# UWB.net
KiCad netlist of a schematic drawn in Altium Designer
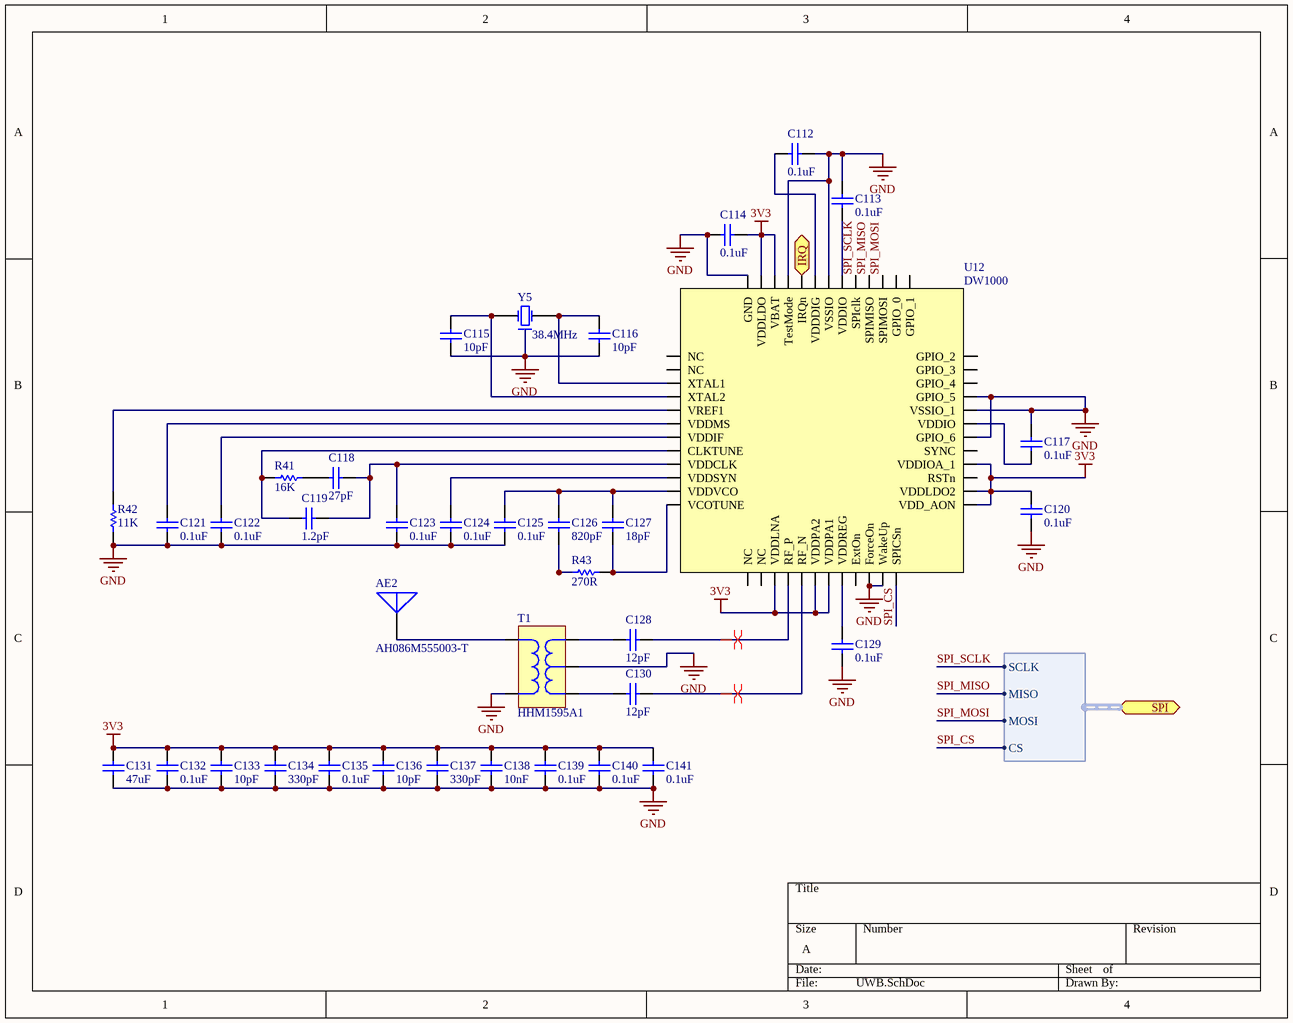
[diagram p0: UWB.SchDoc]

(export (version "E")
  (design (tool "Eeschema 10.0.6"))
  (components
    (comp (ref "AE2")
      (value "AH086M555003-T")
      (footprint "AH086M555003-T")
      (fields (field (name "MANUFACTURER") "Taiyo Yuden"))
      (libsource (lib "Components") (part "AH086M555003-T"))
    )
    (comp (ref "C112")
      (value "0.1uF")
      (footprint "C0402[1005X55]")
      (description "0.1uF 6.3V 10% 0402 (1005 Metric)")
      (fields (field (name "PARTNUMBER") "GRM155R70J104KA01D") (field (name "MANUFACTURER") "Murata"))
      (libsource (lib "Capacitors") (part "CAP_0.1uF_6.3V_0402_10%"))
    )
    (comp (ref "C113")
      (value "0.1uF")
      (footprint "C0402[1005X55]")
      (description "0.1uF 6.3V 10% 0402 (1005 Metric)")
      (fields (field (name "PARTNUMBER") "GRM155R70J104KA01D") (field (name "MANUFACTURER") "Murata"))
      (libsource (lib "Capacitors") (part "CAP_0.1uF_6.3V_0402_10%"))
    )
    (comp (ref "C114")
      (value "0.1uF")
      (footprint "C0402[1005X55]")
      (description "0.1uF 6.3V 10% 0402 (1005 Metric)")
      (fields (field (name "PARTNUMBER") "GRM155R70J104KA01D") (field (name "MANUFACTURER") "Murata"))
      (libsource (lib "Capacitors") (part "CAP_0.1uF_6.3V_0402_10%"))
    )
    (comp (ref "C115")
      (value "10pF")
      (footprint "C0402[1005X55]")
      (description "10pF 50V 1% 0402 (1005 Metric)")
      (fields (field (name "PARTNUMBER") "GRM1555C1H100FA01D") (field (name "MANUFACTURER") "Murata"))
      (libsource (lib "Capacitors") (part "CAP_10pF_50V_0402_1%"))
    )
    (comp (ref "C116")
      (value "10pF")
      (footprint "C0402[1005X55]")
      (description "10pF 50V 1% 0402 (1005 Metric)")
      (fields (field (name "PARTNUMBER") "GRM1555C1H100FA01D") (field (name "MANUFACTURER") "Murata"))
      (libsource (lib "Capacitors") (part "CAP_10pF_50V_0402_1%"))
    )
    (comp (ref "C117")
      (value "0.1uF")
      (footprint "C0402[1005X55]")
      (description "0.1uF 6.3V 10% 0402 (1005 Metric)")
      (fields (field (name "PARTNUMBER") "GRM155R70J104KA01D") (field (name "MANUFACTURER") "Murata"))
      (libsource (lib "Capacitors") (part "CAP_0.1uF_6.3V_0402_10%"))
    )
    (comp (ref "C118")
      (value "27pF")
      (footprint "C0402[1005X55]")
      (description "27pF 50V 1% 0402 (1005 Metric)")
      (fields (field (name "PARTNUMBER") "GRM1555C1H270FA01D") (field (name "MANUFACTURER") "Murata"))
      (libsource (lib "Capacitors") (part "CAP_27pF_50V_0402_1%"))
    )
    (comp (ref "C119")
      (value "1.2pF")
      (footprint "C0402[1005X55]")
      (description "1.2pF 50V 0.05pF 0402 (1005 Metric)")
      (fields (field (name "PARTNUMBER") "GRM1555C1H1R2WA01D") (field (name "MANUFACTURER") "Murata"))
      (libsource (lib "Capacitors") (part "CAP_1.2pF_50V_0402_0.05pF"))
    )
    (comp (ref "C120")
      (value "0.1uF")
      (footprint "C0402[1005X55]")
      (description "0.1uF 6.3V 10% 0402 (1005 Metric)")
      (fields (field (name "PARTNUMBER") "GRM155R70J104KA01D") (field (name "MANUFACTURER") "Murata"))
      (libsource (lib "Capacitors") (part "CAP_0.1uF_6.3V_0402_10%"))
    )
    (comp (ref "C121")
      (value "0.1uF")
      (footprint "C0402[1005X55]")
      (description "0.1uF 6.3V 10% 0402 (1005 Metric)")
      (fields (field (name "PARTNUMBER") "GRM155R70J104KA01D") (field (name "MANUFACTURER") "Murata"))
      (libsource (lib "Capacitors") (part "CAP_0.1uF_6.3V_0402_10%"))
    )
    (comp (ref "C122")
      (value "0.1uF")
      (footprint "C0402[1005X55]")
      (description "0.1uF 6.3V 10% 0402 (1005 Metric)")
      (fields (field (name "PARTNUMBER") "GRM155R70J104KA01D") (field (name "MANUFACTURER") "Murata"))
      (libsource (lib "Capacitors") (part "CAP_0.1uF_6.3V_0402_10%"))
    )
    (comp (ref "C123")
      (value "0.1uF")
      (footprint "C0402[1005X55]")
      (description "0.1uF 6.3V 10% 0402 (1005 Metric)")
      (fields (field (name "PARTNUMBER") "GRM155R70J104KA01D") (field (name "MANUFACTURER") "Murata"))
      (libsource (lib "Capacitors") (part "CAP_0.1uF_6.3V_0402_10%"))
    )
    (comp (ref "C124")
      (value "0.1uF")
      (footprint "C0402[1005X55]")
      (description "0.1uF 6.3V 10% 0402 (1005 Metric)")
      (fields (field (name "PARTNUMBER") "GRM155R70J104KA01D") (field (name "MANUFACTURER") "Murata"))
      (libsource (lib "Capacitors") (part "CAP_0.1uF_6.3V_0402_10%"))
    )
    (comp (ref "C125")
      (value "0.1uF")
      (footprint "C0402[1005X55]")
      (description "0.1uF 6.3V 10% 0402 (1005 Metric)")
      (fields (field (name "PARTNUMBER") "GRM155R70J104KA01D") (field (name "MANUFACTURER") "Murata"))
      (libsource (lib "Capacitors") (part "CAP_0.1uF_6.3V_0402_10%"))
    )
    (comp (ref "C126")
      (value "820pF")
      (footprint "C0402[1005X55]")
      (description "820pF 50V 5% 0402 (1005 Metric)")
      (fields (field (name "PARTNUMBER") "GRM1555C1H821JA01D") (field (name "MANUFACTURER") "Murata"))
      (libsource (lib "Capacitors") (part "CAP_820pF_50V_0402_5%"))
    )
    (comp (ref "C127")
      (value "18pF")
      (footprint "C0402[1005X55]")
      (description "18pF 50V 1% 0402 (1005 Metric)")
      (fields (field (name "PARTNUMBER") "GRM1555C1H180FA01D") (field (name "MANUFACTURER") "Murata"))
      (libsource (lib "Capacitors") (part "CAP_18pF_50V_0402_1%"))
    )
    (comp (ref "C128")
      (value "12pF")
      (footprint "C0402[1005X55]")
      (description "12pF 50V 5% 0402 (1005 Metric)")
      (fields (field (name "PARTNUMBER") "GRM1555C1H120JA01D") (field (name "MANUFACTURER") "Murata"))
      (libsource (lib "Capacitors") (part "CAP_12pF_50V_0402_5%"))
    )
    (comp (ref "C129")
      (value "0.1uF")
      (footprint "C0402[1005X55]")
      (description "0.1uF 6.3V 10% 0402 (1005 Metric)")
      (fields (field (name "PARTNUMBER") "GRM155R70J104KA01D") (field (name "MANUFACTURER") "Murata"))
      (libsource (lib "Capacitors") (part "CAP_0.1uF_6.3V_0402_10%"))
    )
    (comp (ref "C130")
      (value "12pF")
      (footprint "C0402[1005X55]")
      (description "12pF 50V 5% 0402 (1005 Metric)")
      (fields (field (name "PARTNUMBER") "GRM1555C1H120JA01D") (field (name "MANUFACTURER") "Murata"))
      (libsource (lib "Capacitors") (part "CAP_12pF_50V_0402_5%"))
    )
    (comp (ref "C131")
      (value "47uF")
      (footprint "C1206[3216X160]")
      (description "47uF 6.3V 10% 1206 (3216 Metric)")
      (fields (field (name "PARTNUMBER") "GRM31CR60J476KE19L") (field (name "MANUFACTURER") "Murata"))
      (libsource (lib "Capacitors") (part "CAP_47uF_6.3V_1206_10%"))
    )
    (comp (ref "C132")
      (value "0.1uF")
      (footprint "C0402[1005X55]")
      (description "0.1uF 6.3V 10% 0402 (1005 Metric)")
      (fields (field (name "PARTNUMBER") "GRM155R70J104KA01D") (field (name "MANUFACTURER") "Murata"))
      (libsource (lib "Capacitors") (part "CAP_0.1uF_6.3V_0402_10%"))
    )
    (comp (ref "C133")
      (value "10pF")
      (footprint "C0402[1005X55]")
      (description "10pF 50V 1% 0402 (1005 Metric)")
      (fields (field (name "PARTNUMBER") "GRM1555C1H100FA01D") (field (name "MANUFACTURER") "Murata"))
      (libsource (lib "Capacitors") (part "CAP_10pF_50V_0402_1%"))
    )
    (comp (ref "C134")
      (value "330pF")
      (footprint "C0402[1005X55]")
      (description "330pF 50V 5% 0402 (1005 Metric)")
      (fields (field (name "PARTNUMBER") "GRM1555C1H331JA01D") (field (name "MANUFACTURER") "Murata"))
      (libsource (lib "Capacitors") (part "CAP_330pF_50V_0402_5%"))
    )
    (comp (ref "C135")
      (value "0.1uF")
      (footprint "C0402[1005X55]")
      (description "0.1uF 6.3V 10% 0402 (1005 Metric)")
      (fields (field (name "PARTNUMBER") "GRM155R70J104KA01D") (field (name "MANUFACTURER") "Murata"))
      (libsource (lib "Capacitors") (part "CAP_0.1uF_6.3V_0402_10%"))
    )
    (comp (ref "C136")
      (value "10pF")
      (footprint "C0402[1005X55]")
      (description "10pF 50V 1% 0402 (1005 Metric)")
      (fields (field (name "PARTNUMBER") "GRM1555C1H100FA01D") (field (name "MANUFACTURER") "Murata"))
      (libsource (lib "Capacitors") (part "CAP_10pF_50V_0402_1%"))
    )
    (comp (ref "C137")
      (value "330pF")
      (footprint "C0402[1005X55]")
      (description "330pF 50V 5% 0402 (1005 Metric)")
      (fields (field (name "PARTNUMBER") "GRM1555C1H331JA01D") (field (name "MANUFACTURER") "Murata"))
      (libsource (lib "Capacitors") (part "CAP_330pF_50V_0402_5%"))
    )
    (comp (ref "C138")
      (value "10nF")
      (footprint "C0402[1005X55]")
      (description "10nF 50V 10% 0402 (1005 Metric)")
      (fields (field (name "PARTNUMBER") "GCM155R71H103KA55D") (field (name "MANUFACTURER") "Murata"))
      (libsource (lib "Capacitors") (part "CAP_10nF_50V_0402_10%"))
    )
    (comp (ref "C139")
      (value "0.1uF")
      (footprint "C0402[1005X55]")
      (description "0.1uF 6.3V 10% 0402 (1005 Metric)")
      (fields (field (name "PARTNUMBER") "GRM155R70J104KA01D") (field (name "MANUFACTURER") "Murata"))
      (libsource (lib "Capacitors") (part "CAP_0.1uF_6.3V_0402_10%"))
    )
    (comp (ref "C140")
      (value "0.1uF")
      (footprint "C0402[1005X55]")
      (description "0.1uF 6.3V 10% 0402 (1005 Metric)")
      (fields (field (name "PARTNUMBER") "GRM155R70J104KA01D") (field (name "MANUFACTURER") "Murata"))
      (libsource (lib "Capacitors") (part "CAP_0.1uF_6.3V_0402_10%"))
    )
    (comp (ref "C141")
      (value "0.1uF")
      (footprint "C0402[1005X55]")
      (description "0.1uF 6.3V 10% 0402 (1005 Metric)")
      (fields (field (name "PARTNUMBER") "GRM155R70J104KA01D") (field (name "MANUFACTURER") "Murata"))
      (libsource (lib "Capacitors") (part "CAP_0.1uF_6.3V_0402_10%"))
    )
    (comp (ref "R41")
      (value "16K")
      (footprint "R0402[1005]")
      (description "16K 0.063W 1% 0402 (1005 Metric)")
      (fields (field (name "MANUFACTURER") "KOA Speer") (field (name "PARTNUMBER") "RK73H1ETTP1602F"))
      (libsource (lib "Resistors") (part "RES_16K_0402_1%"))
    )
    (comp (ref "R42")
      (value "11K")
      (footprint "R0402[1005]")
      (description "11K 0.063W 1% 0402 (1005 Metric)")
      (fields (field (name "MANUFACTURER") "KOA Speer") (field (name "PARTNUMBER") "RK73H1ETTP1102F"))
      (libsource (lib "Resistors") (part "RES_11K_0402_1%"))
    )
    (comp (ref "R43")
      (value "270R")
      (footprint "R0402[1005]")
      (description "270R 0.063W 1% 0402 (1005 Metric)")
      (fields (field (name "MANUFACTURER") "KOA Speer") (field (name "PARTNUMBER") "RK73H1ETTP2700F"))
      (libsource (lib "Resistors") (part "RES_270R_0402_1%"))
    )
    (comp (ref "T1")
      (value "HHM1595A1")
      (footprint "HHM1595A1")
      (fields (field (name "MANUFACTURER") "TDK"))
      (libsource (lib "Components") (part "HHM1595A1"))
    )
    (comp (ref "U12")
      (value "DW1000")
      (footprint "QFN-48")
      (description "UWB DW1000")
      (fields (field (name "PART NUMBER") "DW1000-I-TR13") (field (name "MANUFACTURER") "Decawave Limited"))
      (libsource (lib "ICs") (part "DW1000"))
    )
    (comp (ref "Y5")
      (value "38.4MHz")
      (footprint "ABRA-ABM10")
      (fields (field (name "PARTNUMBER") "ABM10-165-38.400MHZ-T3") (field (name "MANUFACTURER") "ABRACON"))
      (libsource (lib "Components") (part "ABM10-165-38.400MHZ-T3"))
    )
  )
  (nets
    (net (code "2") (name "/IRQ") (class "Default")
      (node (ref "U12") (pin "45") (pinfunction "IRQn_45") (pintype "passive"))
    )
    (net (code "3") (name "/SPI_CS") (class "Default")
      (node (ref "U12") (pin "24") (pinfunction "SPICSn_24") (pintype "passive"))
    )
    (net (code "4") (name "/SPI_MISO") (class "Default")
      (node (ref "U12") (pin "40") (pinfunction "SPIMISO_40") (pintype "passive"))
    )
    (net (code "5") (name "/SPI_MOSI") (class "Default")
      (node (ref "U12") (pin "39") (pinfunction "SPIMOSI_39") (pintype "passive"))
    )
    (net (code "6") (name "/SPI_SCLK") (class "Default")
      (node (ref "U12") (pin "41") (pinfunction "SPIclk_41") (pintype "passive"))
    )
    (net (code "8") (name "3V3") (class "Default")
      (node (ref "C114") (pin "1") (pinfunction "1_1") (pintype "passive"))
      (node (ref "C120") (pin "2") (pinfunction "2_2") (pintype "passive"))
      (node (ref "C131") (pin "2") (pinfunction "2_2") (pintype "passive"))
      (node (ref "C132") (pin "2") (pinfunction "2_2") (pintype "passive"))
      (node (ref "C133") (pin "2") (pinfunction "2_2") (pintype "passive"))
      (node (ref "C134") (pin "2") (pinfunction "2_2") (pintype "passive"))
      (node (ref "C135") (pin "2") (pinfunction "2_2") (pintype "passive"))
      (node (ref "C136") (pin "2") (pinfunction "2_2") (pintype "passive"))
      (node (ref "C137") (pin "2") (pinfunction "2_2") (pintype "passive"))
      (node (ref "C138") (pin "2") (pinfunction "2_2") (pintype "passive"))
      (node (ref "C139") (pin "2") (pinfunction "2_2") (pintype "passive"))
      (node (ref "C140") (pin "2") (pinfunction "2_2") (pintype "passive"))
      (node (ref "C141") (pin "2") (pinfunction "2_2") (pintype "passive"))
      (node (ref "U12") (pin "15") (pinfunction "VDDLNA_15") (pintype "passive"))
      (node (ref "U12") (pin "18") (pinfunction "VDDPA2_18") (pintype "passive"))
      (node (ref "U12") (pin "19") (pinfunction "VDDPA1_19") (pintype "passive"))
      (node (ref "U12") (pin "25") (pinfunction "VDD_AON_25") (pintype "passive"))
      (node (ref "U12") (pin "26") (pinfunction "VDDLDO2_26") (pintype "passive"))
      (node (ref "U12") (pin "28") (pinfunction "VDDIOA_1_28") (pintype "passive"))
      (node (ref "U12") (pin "47") (pinfunction "VBAT_47") (pintype "passive"))
      (node (ref "U12") (pin "48") (pinfunction "VDDLDO_48") (pintype "passive"))
    )
    (net (code "9") (name "GND") (class "Default")
      (node (ref "C112") (pin "1") (pinfunction "1_1") (pintype "passive"))
      (node (ref "C113") (pin "2") (pinfunction "2_2") (pintype "passive"))
      (node (ref "C114") (pin "2") (pinfunction "2_2") (pintype "passive"))
      (node (ref "C115") (pin "1") (pinfunction "1_1") (pintype "passive"))
      (node (ref "C116") (pin "1") (pinfunction "1_1") (pintype "passive"))
      (node (ref "C117") (pin "2") (pinfunction "2_2") (pintype "passive"))
      (node (ref "C120") (pin "1") (pinfunction "1_1") (pintype "passive"))
      (node (ref "C121") (pin "1") (pinfunction "1_1") (pintype "passive"))
      (node (ref "C122") (pin "1") (pinfunction "1_1") (pintype "passive"))
      (node (ref "C123") (pin "1") (pinfunction "1_1") (pintype "passive"))
      (node (ref "C124") (pin "1") (pinfunction "1_1") (pintype "passive"))
      (node (ref "C125") (pin "1") (pinfunction "1_1") (pintype "passive"))
      (node (ref "C129") (pin "1") (pinfunction "1_1") (pintype "passive"))
      (node (ref "C131") (pin "1") (pinfunction "1_1") (pintype "passive"))
      (node (ref "C132") (pin "1") (pinfunction "1_1") (pintype "passive"))
      (node (ref "C133") (pin "1") (pinfunction "1_1") (pintype "passive"))
      (node (ref "C134") (pin "1") (pinfunction "1_1") (pintype "passive"))
      (node (ref "C135") (pin "1") (pinfunction "1_1") (pintype "passive"))
      (node (ref "C136") (pin "1") (pinfunction "1_1") (pintype "passive"))
      (node (ref "C137") (pin "1") (pinfunction "1_1") (pintype "passive"))
      (node (ref "C138") (pin "1") (pinfunction "1_1") (pintype "passive"))
      (node (ref "C139") (pin "1") (pinfunction "1_1") (pintype "passive"))
      (node (ref "C140") (pin "1") (pinfunction "1_1") (pintype "passive"))
      (node (ref "C141") (pin "1") (pinfunction "1_1") (pintype "passive"))
      (node (ref "R42") (pin "1") (pinfunction "1_1") (pintype "passive"))
      (node (ref "T1") (pin "2") (pinfunction "2_2") (pintype "passive"))
      (node (ref "T1") (pin "5") (pinfunction "5_5") (pintype "passive"))
      (node (ref "U12") (pin "22") (pinfunction "ForceOn_22") (pintype "passive"))
      (node (ref "U12") (pin "23") (pinfunction "WakeUp_23") (pintype "passive"))
      (node (ref "U12") (pin "30") (pinfunction "GPIO_6_30") (pintype "passive"))
      (node (ref "U12") (pin "32") (pinfunction "VSSIO_1_32") (pintype "passive"))
      (node (ref "U12") (pin "33") (pinfunction "GPIO_5_33") (pintype "passive"))
      (node (ref "U12") (pin "43") (pinfunction "VSSIO_43") (pintype "passive"))
      (node (ref "U12") (pin "46") (pinfunction "TestMode_46") (pintype "passive"))
      (node (ref "U12") (pin "49") (pinfunction "GND_49") (pintype "passive"))
      (node (ref "Y5") (pin "2") (pinfunction "2_2") (pintype "passive"))
    )
    (net (code "10") (name "Net-(AE2-Pad1)") (class "Default")
      (node (ref "AE2") (pin "1") (pinfunction "1_1") (pintype "passive"))
      (node (ref "T1") (pin "1") (pinfunction "1_1") (pintype "passive"))
    )
    (net (code "11") (name "Net-(C113-Pad1)") (class "Default")
      (node (ref "C113") (pin "1") (pinfunction "1_1") (pintype "passive"))
      (node (ref "U12") (pin "42") (pinfunction "VDDIO_42") (pintype "passive"))
    )
    (net (code "12") (name "Net-(C117-Pad1)") (class "Default")
      (node (ref "C117") (pin "1") (pinfunction "1_1") (pintype "passive"))
      (node (ref "U12") (pin "31") (pinfunction "VDDIO_31") (pintype "passive"))
    )
    (net (code "13") (name "Net-(C118-Pad2)") (class "Default")
      (node (ref "C118") (pin "2") (pinfunction "2_2") (pintype "passive"))
      (node (ref "R41") (pin "1") (pinfunction "1_1") (pintype "passive"))
    )
    (net (code "14") (name "Net-(C126-Pad1)") (class "Default")
      (node (ref "C126") (pin "1") (pinfunction "1_1") (pintype "passive"))
      (node (ref "R43") (pin "1") (pinfunction "1_1") (pintype "passive"))
    )
    (net (code "15") (name "Net-(C128-Pad1)") (class "Default")
      (node (ref "C128") (pin "1") (pinfunction "1_1") (pintype "passive"))
      (node (ref "T1") (pin "4") (pinfunction "4_4") (pintype "passive"))
    )
    (net (code "16") (name "Net-(C130-Pad1)") (class "Default")
      (node (ref "C130") (pin "1") (pinfunction "1_1") (pintype "passive"))
      (node (ref "T1") (pin "3") (pinfunction "3_3") (pintype "passive"))
    )
    (net (code "17") (name "Net-(U12-CLKTUNE)") (class "Default")
      (node (ref "C119") (pin "2") (pinfunction "2_2") (pintype "passive"))
      (node (ref "R41") (pin "2") (pinfunction "2_2") (pintype "passive"))
      (node (ref "U12") (pin "8") (pinfunction "CLKTUNE_8") (pintype "passive"))
    )
    (net (code "18") (name "Net-(U12-RF_N)") (class "Default")
      (node (ref "C130") (pin "2") (pinfunction "2_2") (pintype "passive"))
      (node (ref "U12") (pin "17") (pinfunction "RF_N_17") (pintype "passive"))
    )
    (net (code "19") (name "Net-(U12-RF_P)") (class "Default")
      (node (ref "C128") (pin "2") (pinfunction "2_2") (pintype "passive"))
      (node (ref "U12") (pin "16") (pinfunction "RF_P_16") (pintype "passive"))
    )
    (net (code "20") (name "Net-(U12-VCOTUNE)") (class "Default")
      (node (ref "C127") (pin "1") (pinfunction "1_1") (pintype "passive"))
      (node (ref "R43") (pin "2") (pinfunction "2_2") (pintype "passive"))
      (node (ref "U12") (pin "12") (pinfunction "VCOTUNE_12") (pintype "passive"))
    )
    (net (code "21") (name "Net-(U12-VDDCLK)") (class "Default")
      (node (ref "C118") (pin "1") (pinfunction "1_1") (pintype "passive"))
      (node (ref "C119") (pin "1") (pinfunction "1_1") (pintype "passive"))
      (node (ref "C123") (pin "2") (pinfunction "2_2") (pintype "passive"))
      (node (ref "U12") (pin "9") (pinfunction "VDDCLK_9") (pintype "passive"))
    )
    (net (code "22") (name "Net-(U12-VDDDIG)") (class "Default")
      (node (ref "C112") (pin "2") (pinfunction "2_2") (pintype "passive"))
      (node (ref "U12") (pin "44") (pinfunction "VDDDIG_44") (pintype "passive"))
    )
    (net (code "23") (name "Net-(U12-VDDIF)") (class "Default")
      (node (ref "C122") (pin "2") (pinfunction "2_2") (pintype "passive"))
      (node (ref "U12") (pin "7") (pinfunction "VDDIF_7") (pintype "passive"))
    )
    (net (code "24") (name "Net-(U12-VDDMS)") (class "Default")
      (node (ref "C121") (pin "2") (pinfunction "2_2") (pintype "passive"))
      (node (ref "U12") (pin "6") (pinfunction "VDDMS_6") (pintype "passive"))
    )
    (net (code "25") (name "Net-(U12-VDDREG)") (class "Default")
      (node (ref "C129") (pin "2") (pinfunction "2_2") (pintype "passive"))
      (node (ref "U12") (pin "20") (pinfunction "VDDREG_20") (pintype "passive"))
    )
    (net (code "26") (name "Net-(U12-VDDSYN)") (class "Default")
      (node (ref "C124") (pin "2") (pinfunction "2_2") (pintype "passive"))
      (node (ref "U12") (pin "10") (pinfunction "VDDSYN_10") (pintype "passive"))
    )
    (net (code "27") (name "Net-(U12-VDDVCO)") (class "Default")
      (node (ref "C125") (pin "2") (pinfunction "2_2") (pintype "passive"))
      (node (ref "C126") (pin "2") (pinfunction "2_2") (pintype "passive"))
      (node (ref "C127") (pin "2") (pinfunction "2_2") (pintype "passive"))
      (node (ref "U12") (pin "11") (pinfunction "VDDVCO_11") (pintype "passive"))
    )
    (net (code "28") (name "Net-(U12-VREF1)") (class "Default")
      (node (ref "R42") (pin "2") (pinfunction "2_2") (pintype "passive"))
      (node (ref "U12") (pin "5") (pinfunction "VREF1_5") (pintype "passive"))
    )
    (net (code "29") (name "Net-(U12-XTAL1)") (class "Default")
      (node (ref "C116") (pin "2") (pinfunction "2_2") (pintype "passive"))
      (node (ref "U12") (pin "3") (pinfunction "XTAL1_3") (pintype "passive"))
      (node (ref "Y5") (pin "3") (pinfunction "X2_3") (pintype "passive"))
    )
    (net (code "30") (name "Net-(U12-XTAL2)") (class "Default")
      (node (ref "C115") (pin "2") (pinfunction "2_2") (pintype "passive"))
      (node (ref "U12") (pin "4") (pinfunction "XTAL2_4") (pintype "passive"))
      (node (ref "Y5") (pin "1") (pinfunction "X1_1") (pintype "passive"))
    )
    (net (code "31") (name "unconnected-(U12-ExtOn-Pad21)") (class "Default")
      (node (ref "U12") (pin "21") (pinfunction "ExtOn_21") (pintype "passive"))
    )
    (net (code "32") (name "unconnected-(U12-GPIO_0-Pad38)") (class "Default")
      (node (ref "U12") (pin "38") (pinfunction "GPIO_0_38") (pintype "passive"))
    )
    (net (code "33") (name "unconnected-(U12-GPIO_1-Pad37)") (class "Default")
      (node (ref "U12") (pin "37") (pinfunction "GPIO_1_37") (pintype "passive"))
    )
    (net (code "34") (name "unconnected-(U12-GPIO_2-Pad36)") (class "Default")
      (node (ref "U12") (pin "36") (pinfunction "GPIO_2_36") (pintype "passive"))
    )
    (net (code "35") (name "unconnected-(U12-GPIO_3-Pad35)") (class "Default")
      (node (ref "U12") (pin "35") (pinfunction "GPIO_3_35") (pintype "passive"))
    )
    (net (code "36") (name "unconnected-(U12-GPIO_4-Pad34)") (class "Default")
      (node (ref "U12") (pin "34") (pinfunction "GPIO_4_34") (pintype "passive"))
    )
    (net (code "37") (name "unconnected-(U12-NC-Pad1)") (class "Default")
      (node (ref "U12") (pin "1") (pinfunction "NC_1") (pintype "passive"))
    )
    (net (code "38") (name "unconnected-(U12-NC-Pad2)") (class "Default")
      (node (ref "U12") (pin "2") (pinfunction "NC_2") (pintype "passive"))
    )
    (net (code "39") (name "unconnected-(U12-NC-Pad13)") (class "Default")
      (node (ref "U12") (pin "13") (pinfunction "NC_13") (pintype "passive"))
    )
    (net (code "40") (name "unconnected-(U12-NC-Pad14)") (class "Default")
      (node (ref "U12") (pin "14") (pinfunction "NC_14") (pintype "passive"))
    )
    (net (code "41") (name "unconnected-(U12-RSTn-Pad27)") (class "Default")
      (node (ref "U12") (pin "27") (pinfunction "RSTn_27") (pintype "passive"))
    )
    (net (code "42") (name "unconnected-(U12-SYNC-Pad29)") (class "Default")
      (node (ref "U12") (pin "29") (pinfunction "SYNC_29") (pintype "passive"))
    )
  )
)
